# controller-schematic.net
KiCad netlist of a schematic drawn in EAGLE
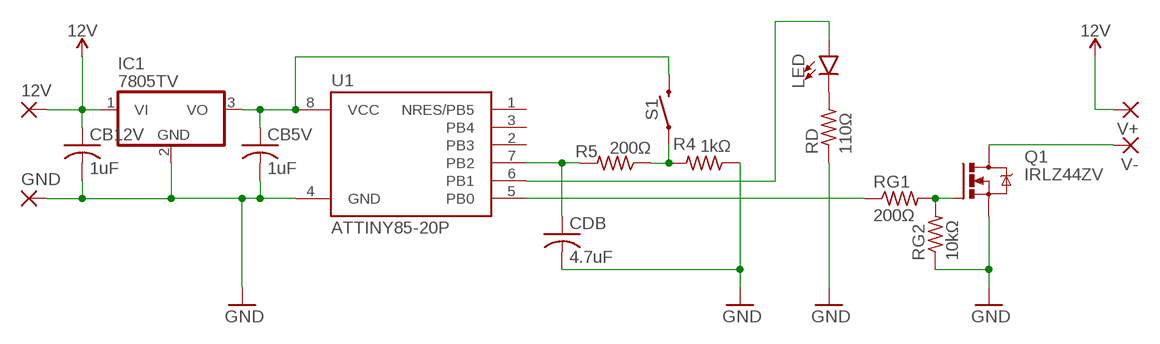
[diagram p0: schematic, sheet 1]

(export (version "E")
  (design (tool "Eeschema 10.0.6"))
  (components
    (comp (ref "12V")
      (value "SMD5")
      (footprint "eagle-import:SMD2,54-5,08")
      (libsource (lib "eagle-import") (part "SMD5"))
    )
    (comp (ref "CB5V")
      (value "1uF")
      (footprint "eagle-import:C050-030X075")
      (libsource (lib "eagle-import") (part "C-US050-030X075"))
    )
    (comp (ref "CB12V")
      (value "1uF")
      (footprint "eagle-import:C050-030X075")
      (libsource (lib "eagle-import") (part "C-US050-030X075"))
    )
    (comp (ref "CDB")
      (value "4.7uF")
      (footprint "eagle-import:C050-030X075")
      (libsource (lib "eagle-import") (part "C-US050-030X075"))
    )
    (comp (ref "GND")
      (value "SMD5")
      (footprint "eagle-import:SMD2,54-5,08")
      (libsource (lib "eagle-import") (part "SMD5"))
    )
    (comp (ref "IC1")
      (value "7805TV")
      (footprint "eagle-import:TO220V")
      (libsource (lib "eagle-import") (part "78TV05"))
    )
    (comp (ref "LED")
      (value "LED3MM")
      (footprint "eagle-import:LED_3MM")
      (libsource (lib "eagle-import") (part "LED3MM"))
    )
    (comp (ref "Q1")
      (value "IRLZ44ZV")
      (footprint "eagle-import:TO220BV")
      (libsource (lib "eagle-import") (part "IRLZ44ZV"))
    )
    (comp (ref "R4")
      (value "1kΩ")
      (footprint "eagle-import:0207_7")
      (libsource (lib "eagle-import") (part "R-US_0207/7"))
    )
    (comp (ref "R5")
      (value "200Ω")
      (footprint "eagle-import:0207_7")
      (libsource (lib "eagle-import") (part "R-US_0207/7"))
    )
    (comp (ref "RD")
      (value "110Ω")
      (footprint "eagle-import:0207_7")
      (libsource (lib "eagle-import") (part "R-US_0207/7"))
    )
    (comp (ref "RG1")
      (value "200Ω")
      (footprint "eagle-import:0207_7")
      (libsource (lib "eagle-import") (part "R-US_0207/7"))
    )
    (comp (ref "RG2")
      (value "10kΩ")
      (footprint "eagle-import:0207_7")
      (libsource (lib "eagle-import") (part "R-US_0207/7"))
    )
    (comp (ref "S1")
      (value "MOMENTARY-SWITCH-SPST-PTH-6.0MM")
      (footprint "eagle-import:TACTILE_SWITCH_PTH_6.0MM")
      (libsource (lib "eagle-import") (part "MOMENTARY-SWITCH-SPST-PTH-6.0MM"))
    )
    (comp (ref "U1")
      (value "ATTINY85-20P")
      (footprint "eagle-import:PDIP08_300MIL")
      (libsource (lib "eagle-import") (part "ATTINY85P-20"))
    )
    (comp (ref "V+")
      (value "SMD5")
      (footprint "eagle-import:SMD2,54-5,08")
      (libsource (lib "eagle-import") (part "SMD5"))
    )
    (comp (ref "V-")
      (value "SMD5")
      (footprint "eagle-import:SMD2,54-5,08")
      (libsource (lib "eagle-import") (part "SMD5"))
    )
  )
  (nets
    (net (code "1") (name "12V") (class "Default")
      (node (ref "12V") (pin "1") (pinfunction "P_1") (pintype "passive"))
      (node (ref "CB12V") (pin "1") (pinfunction "1_1") (pintype "passive"))
      (node (ref "IC1") (pin "1") (pinfunction "VI_1") (pintype "input"))
      (node (ref "V+") (pin "1") (pinfunction "P_1") (pintype "passive"))
    )
    (net (code "2") (name "GND") (class "Default")
      (node (ref "CB12V") (pin "2") (pinfunction "2_2") (pintype "passive"))
      (node (ref "CB5V") (pin "2") (pinfunction "2_2") (pintype "passive"))
      (node (ref "CDB") (pin "2") (pinfunction "2_2") (pintype "passive"))
      (node (ref "GND") (pin "1") (pinfunction "P_1") (pintype "passive"))
      (node (ref "IC1") (pin "2") (pinfunction "GND_2") (pintype "passive"))
      (node (ref "Q1") (pin "S") (pinfunction "S_S") (pintype "passive"))
      (node (ref "R4") (pin "1") (pinfunction "1_1") (pintype "passive"))
      (node (ref "RD") (pin "1") (pinfunction "1_1") (pintype "passive"))
      (node (ref "RG2") (pin "1") (pinfunction "1_1") (pintype "passive"))
      (node (ref "U1") (pin "4") (pinfunction "GND_4") (pintype "power_in"))
    )
    (net (code "3") (name "Net-(IC1-VO)") (class "Default")
      (node (ref "CB5V") (pin "1") (pinfunction "1_1") (pintype "passive"))
      (node (ref "IC1") (pin "3") (pinfunction "VO_3") (pintype "passive"))
      (node (ref "S1") (pin "3") (pinfunction "2_3") (pintype "passive"))
      (node (ref "U1") (pin "8") (pinfunction "VCC_8") (pintype "power_in"))
    )
    (net (code "4") (name "Net-(LED-C)") (class "Default")
      (node (ref "LED") (pin "K") (pinfunction "C_K") (pintype "passive"))
      (node (ref "RD") (pin "2") (pinfunction "2_2") (pintype "passive"))
    )
    (net (code "5") (name "Net-(Q1-PadG)") (class "Default")
      (node (ref "Q1") (pin "G") (pinfunction "G_G") (pintype "passive"))
      (node (ref "RG1") (pin "2") (pinfunction "2_2") (pintype "passive"))
      (node (ref "RG2") (pin "2") (pinfunction "2_2") (pintype "passive"))
    )
    (net (code "6") (name "Net-(R4-Pad2)") (class "Default")
      (node (ref "R4") (pin "2") (pinfunction "2_2") (pintype "passive"))
      (node (ref "R5") (pin "1") (pinfunction "1_1") (pintype "passive"))
      (node (ref "S1") (pin "1") (pinfunction "1_1") (pintype "passive"))
    )
    (net (code "7") (name "Net-(U1-PB0)") (class "Default")
      (node (ref "RG1") (pin "1") (pinfunction "1_1") (pintype "passive"))
      (node (ref "U1") (pin "5") (pinfunction "PB0_5") (pintype "bidirectional"))
    )
    (net (code "8") (name "Net-(U1-PB1)") (class "Default")
      (node (ref "LED") (pin "A") (pinfunction "A_A") (pintype "passive"))
      (node (ref "U1") (pin "6") (pinfunction "PB1_6") (pintype "bidirectional"))
    )
    (net (code "9") (name "Net-(U1-PB2)") (class "Default")
      (node (ref "CDB") (pin "1") (pinfunction "1_1") (pintype "passive"))
      (node (ref "R5") (pin "2") (pinfunction "2_2") (pintype "passive"))
      (node (ref "U1") (pin "7") (pinfunction "PB2_7") (pintype "bidirectional"))
    )
    (net (code "10") (name "Net-(V--P)") (class "Default")
      (node (ref "Q1") (pin "D") (pinfunction "D_D") (pintype "passive"))
      (node (ref "V-") (pin "1") (pinfunction "P_1") (pintype "passive"))
    )
    (net (code "11") (name "unconnected-(U1-NRES{slash}PB5-Pad1)") (class "Default")
      (node (ref "U1") (pin "1") (pinfunction "NRES/PB5_1") (pintype "bidirectional"))
    )
    (net (code "12") (name "unconnected-(U1-PB3-Pad2)") (class "Default")
      (node (ref "U1") (pin "2") (pinfunction "PB3_2") (pintype "bidirectional"))
    )
    (net (code "13") (name "unconnected-(U1-PB4-Pad3)") (class "Default")
      (node (ref "U1") (pin "3") (pinfunction "PB4_3") (pintype "bidirectional"))
    )
  )
)
